# PCB-ARD-XTD1.net
KiCad netlist of a schematic drawn in EAGLE
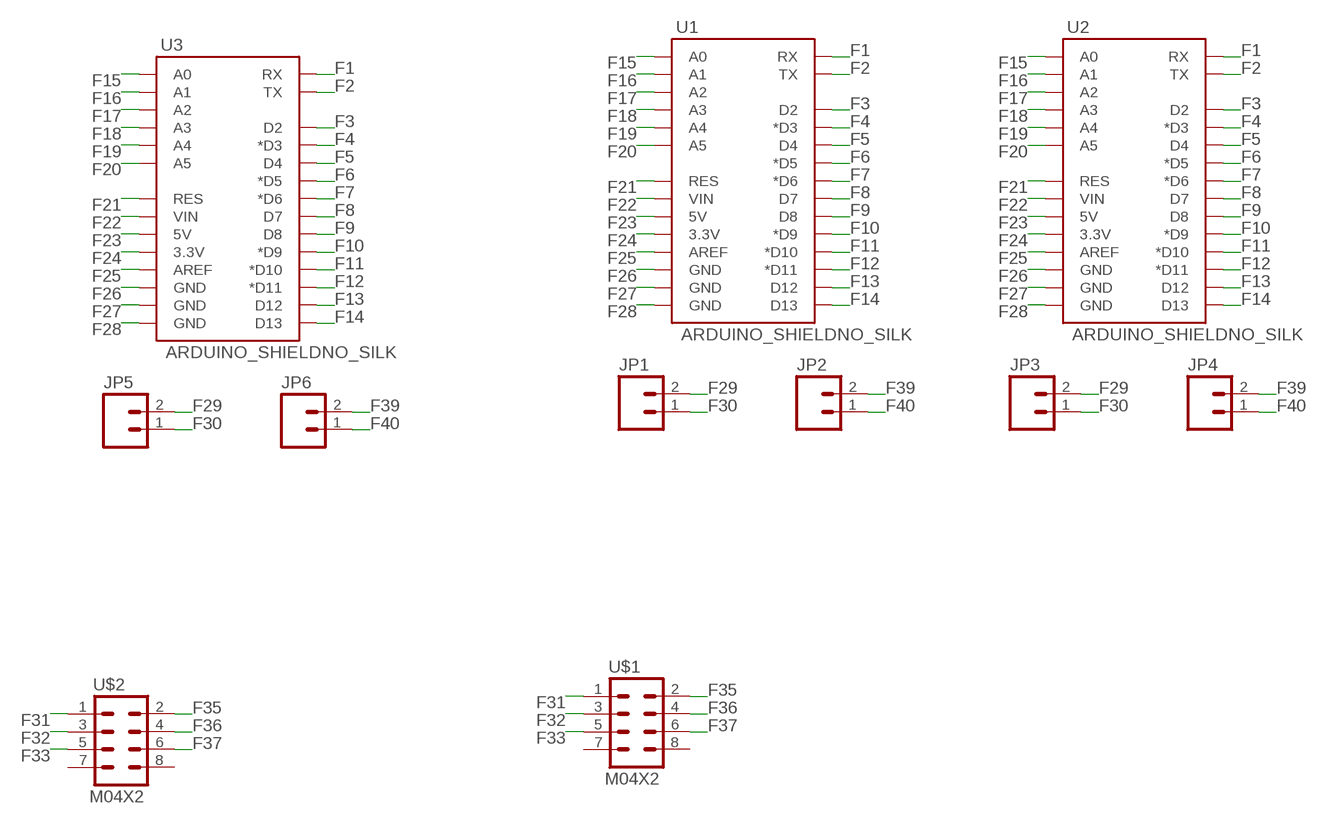
[diagram p0: schematic, sheet 1]

(export (version "E")
  (design (tool "Eeschema 10.0.6"))
  (components
    (comp (ref "JP1")
      (value "M02PTH")
      (footprint "eagle-import:1X02")
      (libsource (lib "eagle-import") (part "M02PTH"))
    )
    (comp (ref "JP2")
      (value "M02PTH")
      (footprint "eagle-import:1X02")
      (libsource (lib "eagle-import") (part "M02PTH"))
    )
    (comp (ref "JP3")
      (value "M02PTH")
      (footprint "eagle-import:1X02")
      (libsource (lib "eagle-import") (part "M02PTH"))
    )
    (comp (ref "JP4")
      (value "M02PTH")
      (footprint "eagle-import:1X02")
      (libsource (lib "eagle-import") (part "M02PTH"))
    )
    (comp (ref "JP5")
      (value "M02PTH")
      (footprint "eagle-import:1X02")
      (libsource (lib "eagle-import") (part "M02PTH"))
    )
    (comp (ref "JP6")
      (value "M02PTH")
      (footprint "eagle-import:1X02")
      (libsource (lib "eagle-import") (part "M02PTH"))
    )
    (comp (ref "U$1")
      (value "M04X2")
      (footprint "eagle-import:2X4")
      (libsource (lib "eagle-import") (part "M04X2"))
    )
    (comp (ref "U$2")
      (value "M04X2")
      (footprint "eagle-import:2X4")
      (libsource (lib "eagle-import") (part "M04X2"))
    )
    (comp (ref "U1")
      (value "ARDUINO_SHIELDNO_SILK")
      (footprint "eagle-import:DUEMILANOVE_VIAS")
      (libsource (lib "eagle-import") (part "ARDUINO_SHIELDNO_SILK"))
    )
    (comp (ref "U2")
      (value "ARDUINO_SHIELDNO_SILK")
      (footprint "eagle-import:DUEMILANOVE_VIAS")
      (libsource (lib "eagle-import") (part "ARDUINO_SHIELDNO_SILK"))
    )
    (comp (ref "U3")
      (value "ARDUINO_SHIELDNO_SILK")
      (footprint "eagle-import:DUEMILANOVE_VIAS")
      (libsource (lib "eagle-import") (part "ARDUINO_SHIELDNO_SILK"))
    )
  )
  (nets
    (net (code "1") (name "/F1") (class "Default")
      (node (ref "U1") (pin "RX") (pinfunction "RX_RX") (pintype "bidirectional"))
      (node (ref "U2") (pin "RX") (pinfunction "RX_RX") (pintype "bidirectional"))
      (node (ref "U3") (pin "RX") (pinfunction "RX_RX") (pintype "bidirectional"))
    )
    (net (code "2") (name "/F2") (class "Default")
      (node (ref "U1") (pin "TX") (pinfunction "TX_TX") (pintype "bidirectional"))
      (node (ref "U2") (pin "TX") (pinfunction "TX_TX") (pintype "bidirectional"))
      (node (ref "U3") (pin "TX") (pinfunction "TX_TX") (pintype "bidirectional"))
    )
    (net (code "3") (name "/F3") (class "Default")
      (node (ref "U1") (pin "D2") (pinfunction "D2_D2") (pintype "bidirectional"))
      (node (ref "U2") (pin "D2") (pinfunction "D2_D2") (pintype "bidirectional"))
      (node (ref "U3") (pin "D2") (pinfunction "D2_D2") (pintype "bidirectional"))
    )
    (net (code "4") (name "/F4") (class "Default")
      (node (ref "U1") (pin "D3") (pinfunction "*D3_D3") (pintype "bidirectional"))
      (node (ref "U2") (pin "D3") (pinfunction "*D3_D3") (pintype "bidirectional"))
      (node (ref "U3") (pin "D3") (pinfunction "*D3_D3") (pintype "bidirectional"))
    )
    (net (code "5") (name "/F5") (class "Default")
      (node (ref "U1") (pin "D4") (pinfunction "D4_D4") (pintype "bidirectional"))
      (node (ref "U2") (pin "D4") (pinfunction "D4_D4") (pintype "bidirectional"))
      (node (ref "U3") (pin "D4") (pinfunction "D4_D4") (pintype "bidirectional"))
    )
    (net (code "6") (name "/F6") (class "Default")
      (node (ref "U1") (pin "D5") (pinfunction "*D5_D5") (pintype "bidirectional"))
      (node (ref "U2") (pin "D5") (pinfunction "*D5_D5") (pintype "bidirectional"))
      (node (ref "U3") (pin "D5") (pinfunction "*D5_D5") (pintype "bidirectional"))
    )
    (net (code "7") (name "/F7") (class "Default")
      (node (ref "U1") (pin "D6") (pinfunction "*D6_D6") (pintype "bidirectional"))
      (node (ref "U2") (pin "D6") (pinfunction "*D6_D6") (pintype "bidirectional"))
      (node (ref "U3") (pin "D6") (pinfunction "*D6_D6") (pintype "bidirectional"))
    )
    (net (code "8") (name "/F8") (class "Default")
      (node (ref "U1") (pin "D7") (pinfunction "D7_D7") (pintype "bidirectional"))
      (node (ref "U2") (pin "D7") (pinfunction "D7_D7") (pintype "bidirectional"))
      (node (ref "U3") (pin "D7") (pinfunction "D7_D7") (pintype "bidirectional"))
    )
    (net (code "9") (name "/F9") (class "Default")
      (node (ref "U1") (pin "D8") (pinfunction "D8_D8") (pintype "bidirectional"))
      (node (ref "U2") (pin "D8") (pinfunction "D8_D8") (pintype "bidirectional"))
      (node (ref "U3") (pin "D8") (pinfunction "D8_D8") (pintype "bidirectional"))
    )
    (net (code "10") (name "/F10") (class "Default")
      (node (ref "U1") (pin "D9") (pinfunction "*D9_D9") (pintype "bidirectional"))
      (node (ref "U2") (pin "D9") (pinfunction "*D9_D9") (pintype "bidirectional"))
      (node (ref "U3") (pin "D9") (pinfunction "*D9_D9") (pintype "bidirectional"))
    )
    (net (code "11") (name "/F11") (class "Default")
      (node (ref "U1") (pin "D10") (pinfunction "*D10_D10") (pintype "bidirectional"))
      (node (ref "U2") (pin "D10") (pinfunction "*D10_D10") (pintype "bidirectional"))
      (node (ref "U3") (pin "D10") (pinfunction "*D10_D10") (pintype "bidirectional"))
    )
    (net (code "12") (name "/F12") (class "Default")
      (node (ref "U1") (pin "D11") (pinfunction "*D11_D11") (pintype "bidirectional"))
      (node (ref "U2") (pin "D11") (pinfunction "*D11_D11") (pintype "bidirectional"))
      (node (ref "U3") (pin "D11") (pinfunction "*D11_D11") (pintype "bidirectional"))
    )
    (net (code "13") (name "/F13") (class "Default")
      (node (ref "U1") (pin "D12") (pinfunction "D12_D12") (pintype "bidirectional"))
      (node (ref "U2") (pin "D12") (pinfunction "D12_D12") (pintype "bidirectional"))
      (node (ref "U3") (pin "D12") (pinfunction "D12_D12") (pintype "bidirectional"))
    )
    (net (code "14") (name "/F14") (class "Default")
      (node (ref "U1") (pin "D13") (pinfunction "D13_D13") (pintype "bidirectional"))
      (node (ref "U2") (pin "D13") (pinfunction "D13_D13") (pintype "bidirectional"))
      (node (ref "U3") (pin "D13") (pinfunction "D13_D13") (pintype "bidirectional"))
    )
    (net (code "15") (name "/F15") (class "Default")
      (node (ref "U1") (pin "A0") (pinfunction "A0_A0") (pintype "bidirectional"))
      (node (ref "U2") (pin "A0") (pinfunction "A0_A0") (pintype "bidirectional"))
      (node (ref "U3") (pin "A0") (pinfunction "A0_A0") (pintype "bidirectional"))
    )
    (net (code "16") (name "/F16") (class "Default")
      (node (ref "U1") (pin "A1") (pinfunction "A1_A1") (pintype "bidirectional"))
      (node (ref "U2") (pin "A1") (pinfunction "A1_A1") (pintype "bidirectional"))
      (node (ref "U3") (pin "A1") (pinfunction "A1_A1") (pintype "bidirectional"))
    )
    (net (code "17") (name "/F17") (class "Default")
      (node (ref "U1") (pin "A2") (pinfunction "A2_A2") (pintype "bidirectional"))
      (node (ref "U2") (pin "A2") (pinfunction "A2_A2") (pintype "bidirectional"))
      (node (ref "U3") (pin "A2") (pinfunction "A2_A2") (pintype "bidirectional"))
    )
    (net (code "18") (name "/F18") (class "Default")
      (node (ref "U1") (pin "A3") (pinfunction "A3_A3") (pintype "bidirectional"))
      (node (ref "U2") (pin "A3") (pinfunction "A3_A3") (pintype "bidirectional"))
      (node (ref "U3") (pin "A3") (pinfunction "A3_A3") (pintype "bidirectional"))
    )
    (net (code "19") (name "/F19") (class "Default")
      (node (ref "U1") (pin "A4") (pinfunction "A4_A4") (pintype "bidirectional"))
      (node (ref "U2") (pin "A4") (pinfunction "A4_A4") (pintype "bidirectional"))
      (node (ref "U3") (pin "A4") (pinfunction "A4_A4") (pintype "bidirectional"))
    )
    (net (code "20") (name "/F20") (class "Default")
      (node (ref "U1") (pin "A5") (pinfunction "A5_A5") (pintype "bidirectional"))
      (node (ref "U2") (pin "A5") (pinfunction "A5_A5") (pintype "bidirectional"))
      (node (ref "U3") (pin "A5") (pinfunction "A5_A5") (pintype "bidirectional"))
    )
    (net (code "21") (name "/F21") (class "Default")
      (node (ref "U1") (pin "RES") (pinfunction "RES_RES") (pintype "bidirectional"))
      (node (ref "U2") (pin "RES") (pinfunction "RES_RES") (pintype "bidirectional"))
      (node (ref "U3") (pin "RES") (pinfunction "RES_RES") (pintype "bidirectional"))
    )
    (net (code "22") (name "/F22") (class "Default")
      (node (ref "U1") (pin "VIN") (pinfunction "VIN_VIN") (pintype "bidirectional"))
      (node (ref "U2") (pin "VIN") (pinfunction "VIN_VIN") (pintype "bidirectional"))
      (node (ref "U3") (pin "VIN") (pinfunction "VIN_VIN") (pintype "bidirectional"))
    )
    (net (code "23") (name "/F23") (class "Default")
      (node (ref "U1") (pin "5V") (pinfunction "5V_5V") (pintype "bidirectional"))
      (node (ref "U2") (pin "5V") (pinfunction "5V_5V") (pintype "bidirectional"))
      (node (ref "U3") (pin "5V") (pinfunction "5V_5V") (pintype "bidirectional"))
    )
    (net (code "24") (name "/F24") (class "Default")
      (node (ref "U1") (pin "3.3V") (pinfunction "3.3V_3.3V") (pintype "bidirectional"))
      (node (ref "U2") (pin "3.3V") (pinfunction "3.3V_3.3V") (pintype "bidirectional"))
      (node (ref "U3") (pin "3.3V") (pinfunction "3.3V_3.3V") (pintype "bidirectional"))
    )
    (net (code "25") (name "/F25") (class "Default")
      (node (ref "U1") (pin "AREF") (pinfunction "AREF_AREF") (pintype "bidirectional"))
      (node (ref "U2") (pin "AREF") (pinfunction "AREF_AREF") (pintype "bidirectional"))
      (node (ref "U3") (pin "AREF") (pinfunction "AREF_AREF") (pintype "bidirectional"))
    )
    (net (code "26") (name "/F26") (class "Default")
      (node (ref "U1") (pin "GND@2") (pinfunction "GND_GND@2") (pintype "bidirectional"))
      (node (ref "U2") (pin "GND@2") (pinfunction "GND_GND@2") (pintype "bidirectional"))
      (node (ref "U3") (pin "GND@2") (pinfunction "GND_GND@2") (pintype "bidirectional"))
    )
    (net (code "27") (name "/F27") (class "Default")
      (node (ref "U1") (pin "GND@1") (pinfunction "GND_GND@1") (pintype "bidirectional"))
      (node (ref "U2") (pin "GND@1") (pinfunction "GND_GND@1") (pintype "bidirectional"))
      (node (ref "U3") (pin "GND@1") (pinfunction "GND_GND@1") (pintype "bidirectional"))
    )
    (net (code "28") (name "/F28") (class "Default")
      (node (ref "U1") (pin "GND@0") (pinfunction "GND_GND@0") (pintype "bidirectional"))
      (node (ref "U2") (pin "GND@0") (pinfunction "GND_GND@0") (pintype "bidirectional"))
      (node (ref "U3") (pin "GND@0") (pinfunction "GND_GND@0") (pintype "bidirectional"))
    )
    (net (code "29") (name "/F29") (class "Default")
      (node (ref "JP1") (pin "2") (pinfunction "2_2") (pintype "passive"))
      (node (ref "JP3") (pin "2") (pinfunction "2_2") (pintype "passive"))
      (node (ref "JP5") (pin "2") (pinfunction "2_2") (pintype "passive"))
    )
    (net (code "30") (name "/F30") (class "Default")
      (node (ref "JP1") (pin "1") (pinfunction "1_1") (pintype "passive"))
      (node (ref "JP3") (pin "1") (pinfunction "1_1") (pintype "passive"))
      (node (ref "JP5") (pin "1") (pinfunction "1_1") (pintype "passive"))
    )
    (net (code "31") (name "/F31") (class "Default")
      (node (ref "U$1") (pin "1") (pinfunction "1_1") (pintype "passive"))
      (node (ref "U$2") (pin "1") (pinfunction "1_1") (pintype "passive"))
    )
    (net (code "32") (name "/F32") (class "Default")
      (node (ref "U$1") (pin "3") (pinfunction "3_3") (pintype "passive"))
      (node (ref "U$2") (pin "3") (pinfunction "3_3") (pintype "passive"))
    )
    (net (code "33") (name "/F33") (class "Default")
      (node (ref "U$1") (pin "5") (pinfunction "5_5") (pintype "passive"))
      (node (ref "U$2") (pin "5") (pinfunction "5_5") (pintype "passive"))
    )
    (net (code "34") (name "/F35") (class "Default")
      (node (ref "U$1") (pin "2") (pinfunction "2_2") (pintype "passive"))
      (node (ref "U$2") (pin "2") (pinfunction "2_2") (pintype "passive"))
    )
    (net (code "35") (name "/F36") (class "Default")
      (node (ref "U$1") (pin "4") (pinfunction "4_4") (pintype "passive"))
      (node (ref "U$2") (pin "4") (pinfunction "4_4") (pintype "passive"))
    )
    (net (code "36") (name "/F37") (class "Default")
      (node (ref "U$1") (pin "6") (pinfunction "6_6") (pintype "passive"))
      (node (ref "U$2") (pin "6") (pinfunction "6_6") (pintype "passive"))
    )
    (net (code "37") (name "/F39") (class "Default")
      (node (ref "JP2") (pin "2") (pinfunction "2_2") (pintype "passive"))
      (node (ref "JP4") (pin "2") (pinfunction "2_2") (pintype "passive"))
      (node (ref "JP6") (pin "2") (pinfunction "2_2") (pintype "passive"))
    )
    (net (code "38") (name "/F40") (class "Default")
      (node (ref "JP2") (pin "1") (pinfunction "1_1") (pintype "passive"))
      (node (ref "JP4") (pin "1") (pinfunction "1_1") (pintype "passive"))
      (node (ref "JP6") (pin "1") (pinfunction "1_1") (pintype "passive"))
    )
    (net (code "39") (name "unconnected-(U$1-Pad7)") (class "Default")
      (node (ref "U$1") (pin "7") (pinfunction "7_7") (pintype "passive"))
    )
    (net (code "40") (name "unconnected-(U$1-Pad8)") (class "Default")
      (node (ref "U$1") (pin "8") (pinfunction "8_8") (pintype "passive"))
    )
    (net (code "41") (name "unconnected-(U$2-Pad7)") (class "Default")
      (node (ref "U$2") (pin "7") (pinfunction "7_7") (pintype "passive"))
    )
    (net (code "42") (name "unconnected-(U$2-Pad8)") (class "Default")
      (node (ref "U$2") (pin "8") (pinfunction "8_8") (pintype "passive"))
    )
  )
)
